# LMR62014_3V7to5V_compact.net
KiCad netlist of a schematic drawn in EAGLE
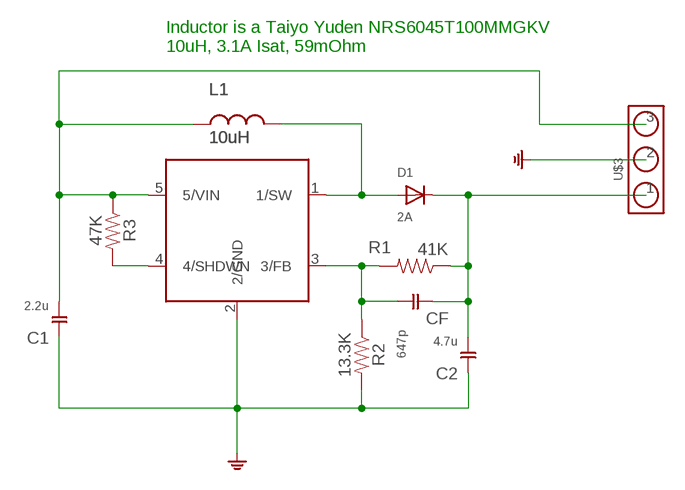
[diagram p0: schematic, sheet 1]

(export (version "E")
  (design (tool "Eeschema 10.0.6"))
  (components
    (comp (ref "C1")
      (value "2.2u")
      (footprint "eagle-import:0603_NORMAL")
      (libsource (lib "eagle-import") (part "CAP_0603"))
    )
    (comp (ref "C2")
      (value "4.7u")
      (footprint "eagle-import:0603_NORMAL")
      (libsource (lib "eagle-import") (part "CAP_0603"))
    )
    (comp (ref "CF")
      (value "647p")
      (footprint "eagle-import:0603_NORMAL")
      (libsource (lib "eagle-import") (part "CAP_0603"))
    )
    (comp (ref "D1")
      (value "2A")
      (footprint "eagle-import:SOD-123FL")
      (libsource (lib "eagle-import") (part "DIODE_SOD-123FL"))
    )
    (comp (ref "L1")
      (value "10uH")
      (footprint "eagle-import:INDUCTOR_SMALL")
      (libsource (lib "eagle-import") (part "INDUCTOR_SMALL"))
    )
    (comp (ref "R1")
      (value "41K")
      (footprint "eagle-import:0603_NORMAL")
      (libsource (lib "eagle-import") (part "RESISTOR_0603_TYPICAL"))
    )
    (comp (ref "R2")
      (value "13.3K")
      (footprint "eagle-import:0603_NORMAL")
      (libsource (lib "eagle-import") (part "RESISTOR_0603_TYPICAL"))
    )
    (comp (ref "R3")
      (value "47K")
      (footprint "eagle-import:0603_NORMAL")
      (libsource (lib "eagle-import") (part "RESISTOR_0603_TYPICAL"))
    )
    (comp (ref "U$1")
      (value "LMR62014")
      (footprint "eagle-import:SOT23-5")
      (libsource (lib "eagle-import") (part "LMR62014"))
    )
    (comp (ref "U$3")
      (value "HEADER_1X32.54")
      (footprint "eagle-import:1X3_.1__2.54MM")
      (libsource (lib "eagle-import") (part "HEADER_1X32.54"))
    )
  )
  (nets
    (net (code "1") (name "GND") (class "Default")
      (node (ref "C1") (pin "1") (pinfunction "1_1") (pintype "passive"))
      (node (ref "C2") (pin "1") (pinfunction "1_1") (pintype "passive"))
      (node (ref "R2") (pin "2") (pinfunction "2_2") (pintype "passive"))
      (node (ref "U$1") (pin "2") (pinfunction "2/GND_2") (pintype "bidirectional"))
      (node (ref "U$3") (pin "2") (pinfunction "P$2_2") (pintype "bidirectional"))
    )
    (net (code "2") (name "Net-(L1-1)") (class "Default")
      (node (ref "C1") (pin "2") (pinfunction "2_2") (pintype "passive"))
      (node (ref "L1") (pin "P$1") (pinfunction "1_P$1") (pintype "bidirectional"))
      (node (ref "R3") (pin "1") (pinfunction "1_1") (pintype "passive"))
      (node (ref "U$1") (pin "5") (pinfunction "5/VIN_5") (pintype "bidirectional"))
      (node (ref "U$3") (pin "3") (pinfunction "P$3_3") (pintype "bidirectional"))
    )
    (net (code "3") (name "Net-(L1-2)") (class "Default")
      (node (ref "D1") (pin "A") (pinfunction "A_A") (pintype "passive"))
      (node (ref "L1") (pin "P$2") (pinfunction "2_P$2") (pintype "bidirectional"))
      (node (ref "U$1") (pin "1") (pinfunction "1/SW_1") (pintype "bidirectional"))
    )
    (net (code "4") (name "Net-(U$1-3{slash}FB)") (class "Default")
      (node (ref "CF") (pin "2") (pinfunction "2_2") (pintype "passive"))
      (node (ref "R1") (pin "2") (pinfunction "2_2") (pintype "passive"))
      (node (ref "R2") (pin "1") (pinfunction "1_1") (pintype "passive"))
      (node (ref "U$1") (pin "3") (pinfunction "3/FB_3") (pintype "bidirectional"))
    )
    (net (code "5") (name "Net-(U$1-4{slash}SHDWN)") (class "Default")
      (node (ref "R3") (pin "2") (pinfunction "2_2") (pintype "passive"))
      (node (ref "U$1") (pin "4") (pinfunction "4/SHDWN_4") (pintype "bidirectional"))
    )
    (net (code "6") (name "Net-(U$3-P$1)") (class "Default")
      (node (ref "C2") (pin "2") (pinfunction "2_2") (pintype "passive"))
      (node (ref "CF") (pin "1") (pinfunction "1_1") (pintype "passive"))
      (node (ref "D1") (pin "C") (pinfunction "C_C") (pintype "passive"))
      (node (ref "R1") (pin "1") (pinfunction "1_1") (pintype "passive"))
      (node (ref "U$3") (pin "1") (pinfunction "P$1_1") (pintype "bidirectional"))
    )
  )
)
